# RasPi-BplusHAT.net
KiCad netlist of a schematic drawn in EAGLE
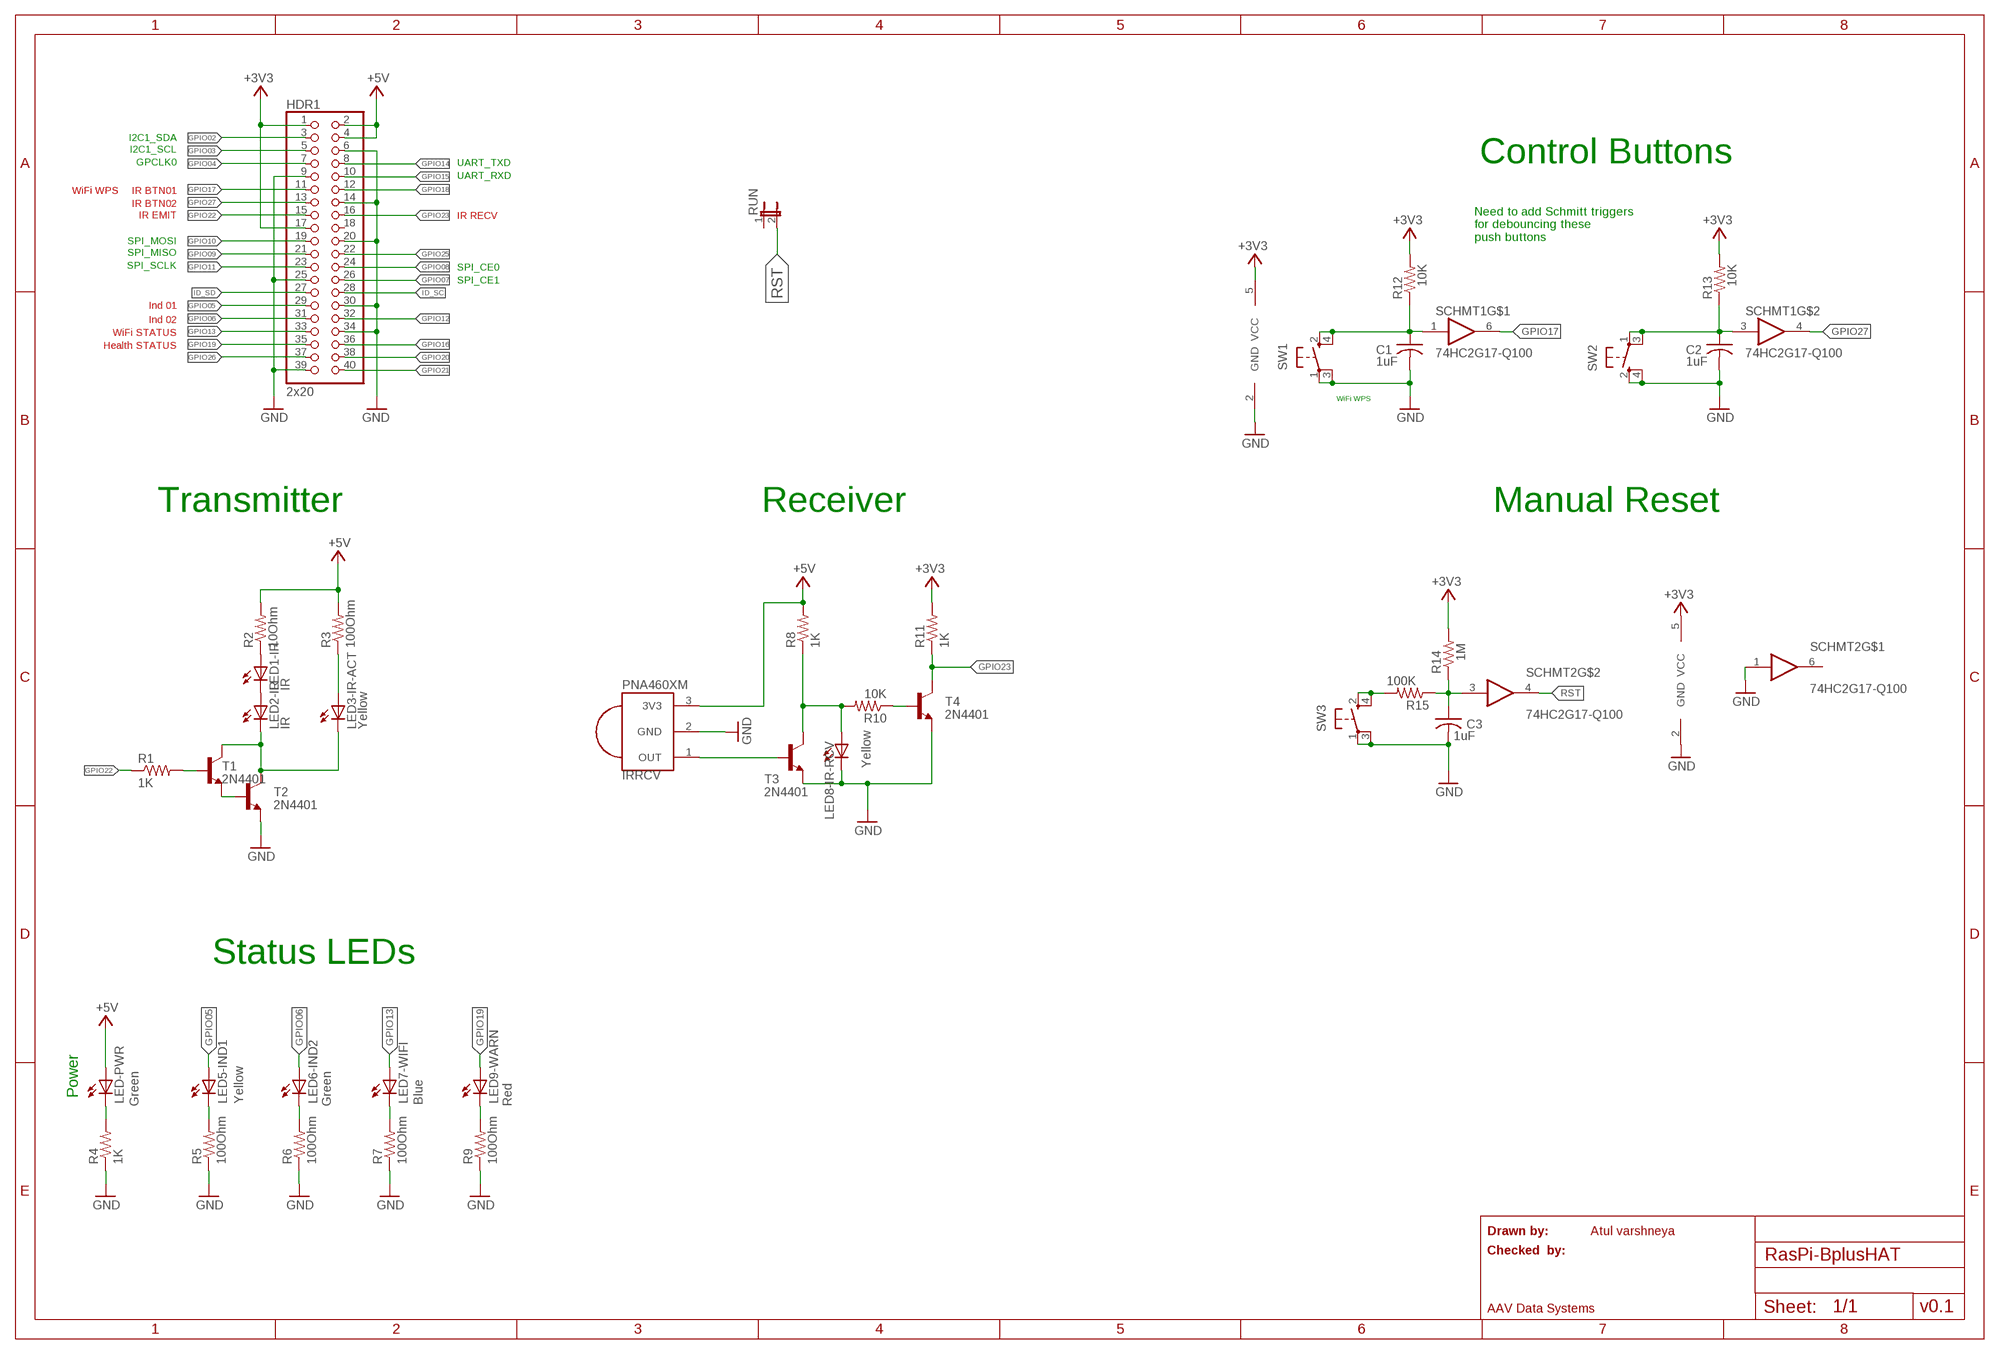
[diagram p0: schematic, sheet 1]

(export (version "E")
  (design (tool "Eeschema 10.0.6"))
  (components
    (comp (ref "C1")
      (value "1uF")
      (footprint "eagle-import:C0805")
      (fields (field (name "MPN") "MC0805B104K160CT"))
      (libsource (lib "eagle-import") (part "C-USC0805"))
    )
    (comp (ref "C2")
      (value "1uF")
      (footprint "eagle-import:C0805")
      (fields (field (name "MPN") "MC0805B104K160CT"))
      (libsource (lib "eagle-import") (part "C-USC0805"))
    )
    (comp (ref "C3")
      (value "1uF")
      (footprint "eagle-import:C0805")
      (fields (field (name "MPN") "MC0805B104K160CT"))
      (libsource (lib "eagle-import") (part "C-USC0805"))
    )
    (comp (ref "HDR1")
      (value "2x20")
      (footprint "eagle-import:2X20")
      (libsource (lib "eagle-import") (part "PINHD-2X20"))
    )
    (comp (ref "IRRCV")
      (value "PNA460XM")
      (footprint "eagle-import:PNA460XM")
      (fields (field (name "MPN") "TSOP38238"))
      (libsource (lib "eagle-import") (part "PNA460XM"))
    )
    (comp (ref "LED-PWR")
      (value "Green")
      (footprint "eagle-import:CHIPLED_0805")
      (fields (field (name "MPN") "150080GS75000"))
      (libsource (lib "eagle-import") (part "LEDCHIPLED_0805"))
    )
    (comp (ref "LED1-IR")
      (value "IR")
      (footprint "eagle-import:MICRO-SIDELED")
      (fields (field (name "MPN") "VSMB2943SLX01"))
      (libsource (lib "eagle-import") (part "LEDMICRO-SIDELED"))
    )
    (comp (ref "LED2-IR")
      (value "IR")
      (footprint "eagle-import:MICRO-SIDELED")
      (fields (field (name "MPN") "VSMB2943SLX01"))
      (libsource (lib "eagle-import") (part "LEDMICRO-SIDELED"))
    )
    (comp (ref "LED3-IR-ACT")
      (value "Yellow")
      (footprint "eagle-import:CHIPLED_0805")
      (fields (field (name "MPN") "150080YS75000"))
      (libsource (lib "eagle-import") (part "LEDCHIPLED_0805"))
    )
    (comp (ref "LED5-IND1")
      (value "Yellow")
      (footprint "eagle-import:CHIPLED_0805")
      (fields (field (name "MPN") "150080YS75000"))
      (libsource (lib "eagle-import") (part "LEDCHIPLED_0805"))
    )
    (comp (ref "LED6-IND2")
      (value "Green")
      (footprint "eagle-import:CHIPLED_0805")
      (fields (field (name "MPN") "150080GS75000"))
      (libsource (lib "eagle-import") (part "LEDCHIPLED_0805"))
    )
    (comp (ref "LED7-WIFI")
      (value "Blue")
      (footprint "eagle-import:CHIPLED_0805")
      (fields (field (name "MPN") "150080BS75000"))
      (libsource (lib "eagle-import") (part "LEDCHIPLED_0805"))
    )
    (comp (ref "LED8-IR-RCV")
      (value "Yellow")
      (footprint "eagle-import:CHIPLED_0805")
      (fields (field (name "MPN") "150080YS75000"))
      (libsource (lib "eagle-import") (part "LEDCHIPLED_0805"))
    )
    (comp (ref "LED9-WARN")
      (value "Red")
      (footprint "eagle-import:CHIPLED_0805")
      (fields (field (name "MPN") "150080RS75000"))
      (libsource (lib "eagle-import") (part "LEDCHIPLED_0805"))
    )
    (comp (ref "R1")
      (value "1K")
      (footprint "eagle-import:R0805")
      (fields (field (name "MF") "VISHAY/DALE") (field (name "MPN") "CRCW08051K00FKEA"))
      (libsource (lib "eagle-import") (part "R-US_R0805"))
    )
    (comp (ref "R2")
      (value "10Ohm")
      (footprint "eagle-import:R0805")
      (fields (field (name "MF") "VISHAY/DALE") (field (name "MPN") "CRCW080510R0FKEA"))
      (libsource (lib "eagle-import") (part "R-US_R0805"))
    )
    (comp (ref "R3")
      (value "100Ohm")
      (footprint "eagle-import:R0805")
      (fields (field (name "MF") "VISHAY/DALE") (field (name "MPN") "CRCW0805100RFKEA"))
      (libsource (lib "eagle-import") (part "R-US_R0805"))
    )
    (comp (ref "R4")
      (value "1K")
      (footprint "eagle-import:R0805")
      (fields (field (name "MF") "VISHAY/DALE") (field (name "MPN") "CRCW08051K00FKEA"))
      (libsource (lib "eagle-import") (part "R-US_R0805"))
    )
    (comp (ref "R5")
      (value "100Ohm")
      (footprint "eagle-import:R0805")
      (fields (field (name "MF") "VISHAY/DALE") (field (name "MPN") "CRCW0805100RFKEA"))
      (libsource (lib "eagle-import") (part "R-US_R0805"))
    )
    (comp (ref "R6")
      (value "100Ohm")
      (footprint "eagle-import:R0805")
      (fields (field (name "MF") "VISHAY/DALE") (field (name "MPN") "CRCW0805100RFKEA"))
      (libsource (lib "eagle-import") (part "R-US_R0805"))
    )
    (comp (ref "R7")
      (value "100Ohm")
      (footprint "eagle-import:R0805")
      (fields (field (name "MF") "VISHAY/DALE") (field (name "MPN") "CRCW0805100RFKEA"))
      (libsource (lib "eagle-import") (part "R-US_R0805"))
    )
    (comp (ref "R8")
      (value "1K")
      (footprint "eagle-import:R0805")
      (fields (field (name "MF") "VISHAY/DALE") (field (name "MPN") "CRCW08051K00FKEA"))
      (libsource (lib "eagle-import") (part "R-US_R0805"))
    )
    (comp (ref "R9")
      (value "100Ohm")
      (footprint "eagle-import:R0805")
      (fields (field (name "MF") "VISHAY/DALE") (field (name "MPN") "CRCW0805100RFKEA"))
      (libsource (lib "eagle-import") (part "R-US_R0805"))
    )
    (comp (ref "R10")
      (value "10K")
      (footprint "eagle-import:R0805")
      (fields (field (name "MF") "VISHAY/DALE") (field (name "MPN") "CRCW080510K0FKEA"))
      (libsource (lib "eagle-import") (part "R-US_R0805"))
    )
    (comp (ref "R11")
      (value "1K")
      (footprint "eagle-import:R0805")
      (fields (field (name "MF") "VISHAY/DALE") (field (name "MPN") "CRCW08051K00FKEA"))
      (libsource (lib "eagle-import") (part "R-US_R0805"))
    )
    (comp (ref "R12")
      (value "10K")
      (footprint "eagle-import:R0805")
      (fields (field (name "MF") "VISHAY/DALE") (field (name "MPN") "CRCW080510K0FKEA"))
      (libsource (lib "eagle-import") (part "R-US_R0805"))
    )
    (comp (ref "R13")
      (value "10K")
      (footprint "eagle-import:R0805")
      (fields (field (name "MF") "VISHAY/DALE") (field (name "MPN") "CRCW080510K0FKEA"))
      (libsource (lib "eagle-import") (part "R-US_R0805"))
    )
    (comp (ref "R14")
      (value "1M")
      (footprint "eagle-import:R0805")
      (fields (field (name "MF") "VISHAY/DALE") (field (name "MPN") "CRCW08051M00FKEA"))
      (libsource (lib "eagle-import") (part "R-US_R0805"))
    )
    (comp (ref "R15")
      (value "100K")
      (footprint "eagle-import:R0805")
      (fields (field (name "MF") "VISHAY/DALE") (field (name "MPN") "CRCW0805100KFKEA"))
      (libsource (lib "eagle-import") (part "R-US_R0805"))
    )
    (comp (ref "RUN")
      (value "RST")
      (footprint "eagle-import:JP1")
      (fields (field (name "MPN") "2211S-02G"))
      (libsource (lib "eagle-import") (part "JP1E"))
    )
    (comp (ref "SCHMT1")
      (value "74HC2G17-Q100")
      (footprint "eagle-import:SC-70-6L")
      (fields (field (name "MPN") "74HC2G17GW,125") (field (name "OC_NEWARK") "71R2196"))
      (libsource (lib "eagle-import") (part "74HC2G17-Q100"))
    )
    (comp (ref "SCHMT2")
      (value "74HC2G17-Q100")
      (footprint "eagle-import:SC-70-6L")
      (fields (field (name "MPN") "74HC2G17GW,125") (field (name "OC_NEWARK") "71R2196"))
      (libsource (lib "eagle-import") (part "74HC2G17-Q100"))
    )
    (comp (ref "SW1")
      (value "SPST_TACT-KMR2")
      (footprint "eagle-import:KMR2")
      (libsource (lib "eagle-import") (part "SPST_TACT-KMR2"))
    )
    (comp (ref "SW2")
      (value "SPST_TACT-KMR2")
      (footprint "eagle-import:KMR2")
      (libsource (lib "eagle-import") (part "SPST_TACT-KMR2"))
    )
    (comp (ref "SW3")
      (value "SPST_TACT-KMR2")
      (footprint "eagle-import:KMR2")
      (libsource (lib "eagle-import") (part "SPST_TACT-KMR2"))
    )
    (comp (ref "T1")
      (value "2N4401")
      (footprint "eagle-import:SOT23-BEC")
      (fields (field (name "MPN") "MMBT4401-TP"))
      (libsource (lib "eagle-import") (part "transistor-neu-to92_-NPN-SOT23-BECMMBT4401LT1"))
    )
    (comp (ref "T2")
      (value "2N4401")
      (footprint "eagle-import:SOT23-BEC")
      (fields (field (name "MPN") "MMBT4401-TP"))
      (libsource (lib "eagle-import") (part "transistor-neu-to92_-NPN-SOT23-BECMMBT4401LT1"))
    )
    (comp (ref "T3")
      (value "2N4401")
      (footprint "eagle-import:SOT23-BEC")
      (fields (field (name "MPN") "MMBT4401-TP"))
      (libsource (lib "eagle-import") (part "-NPN-SOT23-BECMMBT4401LT1"))
    )
    (comp (ref "T4")
      (value "2N4401")
      (footprint "eagle-import:SOT23-BEC")
      (fields (field (name "MPN") "MMBT4401-TP"))
      (libsource (lib "eagle-import") (part "-NPN-SOT23-BECMMBT4401LT1"))
    )
  )
  (nets
    (net (code "1") (name "+3V3") (class "Default")
      (node (ref "HDR1") (pin "1") (pinfunction "1_1") (pintype "passive"))
      (node (ref "HDR1") (pin "17") (pinfunction "17_17") (pintype "passive"))
      (node (ref "R11") (pin "2") (pinfunction "2_2") (pintype "passive"))
      (node (ref "R12") (pin "2") (pinfunction "2_2") (pintype "passive"))
      (node (ref "R13") (pin "2") (pinfunction "2_2") (pintype "passive"))
      (node (ref "R14") (pin "2") (pinfunction "2_2") (pintype "passive"))
      (node (ref "SCHMT1") (pin "5") (pinfunction "VCC_5") (pintype "bidirectional"))
      (node (ref "SCHMT2") (pin "5") (pinfunction "VCC_5") (pintype "bidirectional"))
    )
    (net (code "2") (name "+5V") (class "Default")
      (node (ref "HDR1") (pin "2") (pinfunction "2_2") (pintype "passive"))
      (node (ref "HDR1") (pin "4") (pinfunction "4_4") (pintype "passive"))
      (node (ref "IRRCV") (pin "3") (pinfunction "3V3_3") (pintype "power_in"))
      (node (ref "LED-PWR") (pin "A") (pinfunction "A_A") (pintype "passive"))
      (node (ref "R2") (pin "2") (pinfunction "2_2") (pintype "passive"))
      (node (ref "R3") (pin "2") (pinfunction "2_2") (pintype "passive"))
      (node (ref "R8") (pin "2") (pinfunction "2_2") (pintype "passive"))
    )
    (net (code "3") (name "GND") (class "Default")
      (node (ref "C1") (pin "2") (pinfunction "2_2") (pintype "passive"))
      (node (ref "C2") (pin "2") (pinfunction "2_2") (pintype "passive"))
      (node (ref "C3") (pin "2") (pinfunction "2_2") (pintype "passive"))
      (node (ref "HDR1") (pin "14") (pinfunction "14_14") (pintype "passive"))
      (node (ref "HDR1") (pin "20") (pinfunction "20_20") (pintype "passive"))
      (node (ref "HDR1") (pin "25") (pinfunction "25_25") (pintype "passive"))
      (node (ref "HDR1") (pin "30") (pinfunction "30_30") (pintype "passive"))
      (node (ref "HDR1") (pin "34") (pinfunction "34_34") (pintype "passive"))
      (node (ref "HDR1") (pin "39") (pinfunction "39_39") (pintype "passive"))
      (node (ref "HDR1") (pin "6") (pinfunction "6_6") (pintype "passive"))
      (node (ref "HDR1") (pin "9") (pinfunction "9_9") (pintype "passive"))
      (node (ref "IRRCV") (pin "2") (pinfunction "GND_2") (pintype "power_in"))
      (node (ref "LED8-IR-RCV") (pin "C") (pinfunction "C_C") (pintype "passive"))
      (node (ref "R4") (pin "1") (pinfunction "1_1") (pintype "passive"))
      (node (ref "R5") (pin "1") (pinfunction "1_1") (pintype "passive"))
      (node (ref "R6") (pin "1") (pinfunction "1_1") (pintype "passive"))
      (node (ref "R7") (pin "1") (pinfunction "1_1") (pintype "passive"))
      (node (ref "R9") (pin "1") (pinfunction "1_1") (pintype "passive"))
      (node (ref "SCHMT1") (pin "2") (pinfunction "GND_2") (pintype "bidirectional"))
      (node (ref "SCHMT2") (pin "1") (pinfunction "I_1") (pintype "input"))
      (node (ref "SCHMT2") (pin "2") (pinfunction "GND_2") (pintype "bidirectional"))
      (node (ref "SW1") (pin "1") (pinfunction "P_1") (pintype "passive"))
      (node (ref "SW1") (pin "3") (pinfunction "P1_3") (pintype "passive"))
      (node (ref "SW2") (pin "2") (pinfunction "S_2") (pintype "passive"))
      (node (ref "SW2") (pin "4") (pinfunction "S1_4") (pintype "passive"))
      (node (ref "SW3") (pin "1") (pinfunction "P_1") (pintype "passive"))
      (node (ref "SW3") (pin "3") (pinfunction "P1_3") (pintype "passive"))
      (node (ref "T2") (pin "E") (pinfunction "E_E") (pintype "passive"))
      (node (ref "T3") (pin "E") (pinfunction "E_E") (pintype "passive"))
      (node (ref "T4") (pin "E") (pinfunction "E_E") (pintype "passive"))
    )
    (net (code "4") (name "GPIO02") (class "Default")
      (node (ref "HDR1") (pin "3") (pinfunction "3_3") (pintype "passive"))
    )
    (net (code "5") (name "GPIO03") (class "Default")
      (node (ref "HDR1") (pin "5") (pinfunction "5_5") (pintype "passive"))
    )
    (net (code "6") (name "GPIO04") (class "Default")
      (node (ref "HDR1") (pin "7") (pinfunction "7_7") (pintype "passive"))
    )
    (net (code "7") (name "GPIO05") (class "Default")
      (node (ref "HDR1") (pin "29") (pinfunction "29_29") (pintype "passive"))
      (node (ref "LED5-IND1") (pin "A") (pinfunction "A_A") (pintype "passive"))
    )
    (net (code "8") (name "GPIO06") (class "Default")
      (node (ref "HDR1") (pin "31") (pinfunction "31_31") (pintype "passive"))
      (node (ref "LED6-IND2") (pin "A") (pinfunction "A_A") (pintype "passive"))
    )
    (net (code "9") (name "GPIO07") (class "Default")
      (node (ref "HDR1") (pin "26") (pinfunction "26_26") (pintype "passive"))
    )
    (net (code "10") (name "GPIO08") (class "Default")
      (node (ref "HDR1") (pin "24") (pinfunction "24_24") (pintype "passive"))
    )
    (net (code "11") (name "GPIO09") (class "Default")
      (node (ref "HDR1") (pin "21") (pinfunction "21_21") (pintype "passive"))
    )
    (net (code "12") (name "GPIO10") (class "Default")
      (node (ref "HDR1") (pin "19") (pinfunction "19_19") (pintype "passive"))
    )
    (net (code "13") (name "GPIO11") (class "Default")
      (node (ref "HDR1") (pin "23") (pinfunction "23_23") (pintype "passive"))
    )
    (net (code "14") (name "GPIO12") (class "Default")
      (node (ref "HDR1") (pin "32") (pinfunction "32_32") (pintype "passive"))
    )
    (net (code "15") (name "GPIO13") (class "Default")
      (node (ref "HDR1") (pin "33") (pinfunction "33_33") (pintype "passive"))
      (node (ref "LED7-WIFI") (pin "A") (pinfunction "A_A") (pintype "passive"))
    )
    (net (code "16") (name "GPIO14") (class "Default")
      (node (ref "HDR1") (pin "8") (pinfunction "8_8") (pintype "passive"))
    )
    (net (code "17") (name "GPIO15") (class "Default")
      (node (ref "HDR1") (pin "10") (pinfunction "10_10") (pintype "passive"))
    )
    (net (code "18") (name "GPIO16") (class "Default")
      (node (ref "HDR1") (pin "36") (pinfunction "36_36") (pintype "passive"))
    )
    (net (code "19") (name "GPIO17") (class "Default")
      (node (ref "HDR1") (pin "11") (pinfunction "11_11") (pintype "passive"))
      (node (ref "SCHMT1") (pin "6") (pinfunction "O_6") (pintype "output"))
    )
    (net (code "20") (name "GPIO18") (class "Default")
      (node (ref "HDR1") (pin "12") (pinfunction "12_12") (pintype "passive"))
    )
    (net (code "21") (name "GPIO19") (class "Default")
      (node (ref "HDR1") (pin "35") (pinfunction "35_35") (pintype "passive"))
      (node (ref "LED9-WARN") (pin "A") (pinfunction "A_A") (pintype "passive"))
    )
    (net (code "22") (name "GPIO20") (class "Default")
      (node (ref "HDR1") (pin "38") (pinfunction "38_38") (pintype "passive"))
    )
    (net (code "23") (name "GPIO21") (class "Default")
      (node (ref "HDR1") (pin "40") (pinfunction "40_40") (pintype "passive"))
    )
    (net (code "24") (name "GPIO22") (class "Default")
      (node (ref "HDR1") (pin "15") (pinfunction "15_15") (pintype "passive"))
      (node (ref "R1") (pin "1") (pinfunction "1_1") (pintype "passive"))
    )
    (net (code "25") (name "GPIO23") (class "Default")
      (node (ref "HDR1") (pin "16") (pinfunction "16_16") (pintype "passive"))
      (node (ref "R11") (pin "1") (pinfunction "1_1") (pintype "passive"))
      (node (ref "T4") (pin "C") (pinfunction "C_C") (pintype "passive"))
    )
    (net (code "26") (name "GPIO25") (class "Default")
      (node (ref "HDR1") (pin "22") (pinfunction "22_22") (pintype "passive"))
    )
    (net (code "27") (name "GPIO26") (class "Default")
      (node (ref "HDR1") (pin "37") (pinfunction "37_37") (pintype "passive"))
    )
    (net (code "28") (name "GPIO27") (class "Default")
      (node (ref "HDR1") (pin "13") (pinfunction "13_13") (pintype "passive"))
      (node (ref "SCHMT1") (pin "4") (pinfunction "O_4") (pintype "output"))
    )
    (net (code "29") (name "ID_SC") (class "Default")
      (node (ref "HDR1") (pin "28") (pinfunction "28_28") (pintype "passive"))
    )
    (net (code "30") (name "ID_SD") (class "Default")
      (node (ref "HDR1") (pin "27") (pinfunction "27_27") (pintype "passive"))
    )
    (net (code "31") (name "Net-(IRRCV-OUT)") (class "Default")
      (node (ref "IRRCV") (pin "1") (pinfunction "OUT_1") (pintype "output"))
      (node (ref "T3") (pin "B") (pinfunction "B_B") (pintype "passive"))
    )
    (net (code "32") (name "Net-(LED-PWR-PadC)") (class "Default")
      (node (ref "LED-PWR") (pin "C") (pinfunction "C_C") (pintype "passive"))
      (node (ref "R4") (pin "2") (pinfunction "2_2") (pintype "passive"))
    )
    (net (code "33") (name "Net-(LED1-IR-PadA)") (class "Default")
      (node (ref "LED1-IR") (pin "A") (pinfunction "A_A") (pintype "passive"))
      (node (ref "R2") (pin "1") (pinfunction "1_1") (pintype "passive"))
    )
    (net (code "34") (name "Net-(LED1-IR-PadC)") (class "Default")
      (node (ref "LED1-IR") (pin "C") (pinfunction "C_C") (pintype "passive"))
      (node (ref "LED2-IR") (pin "A") (pinfunction "A_A") (pintype "passive"))
    )
    (net (code "35") (name "Net-(LED2-IR-PadC)") (class "Default")
      (node (ref "LED2-IR") (pin "C") (pinfunction "C_C") (pintype "passive"))
      (node (ref "LED3-IR-ACT") (pin "C") (pinfunction "C_C") (pintype "passive"))
      (node (ref "T1") (pin "C") (pinfunction "C_C") (pintype "passive"))
      (node (ref "T2") (pin "C") (pinfunction "C_C") (pintype "passive"))
    )
    (net (code "36") (name "Net-(LED3-IR-ACT-PadA)") (class "Default")
      (node (ref "LED3-IR-ACT") (pin "A") (pinfunction "A_A") (pintype "passive"))
      (node (ref "R3") (pin "1") (pinfunction "1_1") (pintype "passive"))
    )
    (net (code "37") (name "Net-(LED5-IND1-PadC)") (class "Default")
      (node (ref "LED5-IND1") (pin "C") (pinfunction "C_C") (pintype "passive"))
      (node (ref "R5") (pin "2") (pinfunction "2_2") (pintype "passive"))
    )
    (net (code "38") (name "Net-(LED6-IND2-PadC)") (class "Default")
      (node (ref "LED6-IND2") (pin "C") (pinfunction "C_C") (pintype "passive"))
      (node (ref "R6") (pin "2") (pinfunction "2_2") (pintype "passive"))
    )
    (net (code "39") (name "Net-(LED7-WIFI-PadC)") (class "Default")
      (node (ref "LED7-WIFI") (pin "C") (pinfunction "C_C") (pintype "passive"))
      (node (ref "R7") (pin "2") (pinfunction "2_2") (pintype "passive"))
    )
    (net (code "40") (name "Net-(LED8-IR-RCV-PadA)") (class "Default")
      (node (ref "LED8-IR-RCV") (pin "A") (pinfunction "A_A") (pintype "passive"))
      (node (ref "R10") (pin "2") (pinfunction "2_2") (pintype "passive"))
      (node (ref "R8") (pin "1") (pinfunction "1_1") (pintype "passive"))
      (node (ref "T3") (pin "C") (pinfunction "C_C") (pintype "passive"))
    )
    (net (code "41") (name "Net-(LED9-WARN-PadC)") (class "Default")
      (node (ref "LED9-WARN") (pin "C") (pinfunction "C_C") (pintype "passive"))
      (node (ref "R9") (pin "2") (pinfunction "2_2") (pintype "passive"))
    )
    (net (code "42") (name "Net-(R1-Pad2)") (class "Default")
      (node (ref "R1") (pin "2") (pinfunction "2_2") (pintype "passive"))
      (node (ref "T1") (pin "B") (pinfunction "B_B") (pintype "passive"))
    )
    (net (code "43") (name "Net-(R10-Pad1)") (class "Default")
      (node (ref "R10") (pin "1") (pinfunction "1_1") (pintype "passive"))
      (node (ref "T4") (pin "B") (pinfunction "B_B") (pintype "passive"))
    )
    (net (code "44") (name "Net-(SCHMT1A-I)") (class "Default")
      (node (ref "C1") (pin "1") (pinfunction "1_1") (pintype "passive"))
      (node (ref "R12") (pin "1") (pinfunction "1_1") (pintype "passive"))
      (node (ref "SCHMT1") (pin "1") (pinfunction "I_1") (pintype "input"))
      (node (ref "SW1") (pin "2") (pinfunction "S_2") (pintype "passive"))
      (node (ref "SW1") (pin "4") (pinfunction "S1_4") (pintype "passive"))
    )
    (net (code "45") (name "Net-(SCHMT1B-I)") (class "Default")
      (node (ref "C2") (pin "1") (pinfunction "1_1") (pintype "passive"))
      (node (ref "R13") (pin "1") (pinfunction "1_1") (pintype "passive"))
      (node (ref "SCHMT1") (pin "3") (pinfunction "I_3") (pintype "input"))
      (node (ref "SW2") (pin "1") (pinfunction "P_1") (pintype "passive"))
      (node (ref "SW2") (pin "3") (pinfunction "P1_3") (pintype "passive"))
    )
    (net (code "46") (name "Net-(SCHMT2B-I)") (class "Default")
      (node (ref "C3") (pin "1") (pinfunction "1_1") (pintype "passive"))
      (node (ref "R14") (pin "1") (pinfunction "1_1") (pintype "passive"))
      (node (ref "R15") (pin "1") (pinfunction "1_1") (pintype "passive"))
      (node (ref "SCHMT2") (pin "3") (pinfunction "I_3") (pintype "input"))
    )
    (net (code "47") (name "Net-(SW3-S)") (class "Default")
      (node (ref "R15") (pin "2") (pinfunction "2_2") (pintype "passive"))
      (node (ref "SW3") (pin "2") (pinfunction "S_2") (pintype "passive"))
      (node (ref "SW3") (pin "4") (pinfunction "S1_4") (pintype "passive"))
    )
    (net (code "48") (name "Net-(T1-PadE)") (class "Default")
      (node (ref "T1") (pin "E") (pinfunction "E_E") (pintype "passive"))
      (node (ref "T2") (pin "B") (pinfunction "B_B") (pintype "passive"))
    )
    (net (code "49") (name "RST") (class "Default")
      (node (ref "RUN") (pin "2") (pinfunction "2_2") (pintype "passive"))
      (node (ref "SCHMT2") (pin "4") (pinfunction "O_4") (pintype "output"))
    )
    (net (code "50") (name "unconnected-(HDR1-Pad18)") (class "Default")
      (node (ref "HDR1") (pin "18") (pinfunction "18_18") (pintype "passive"))
    )
    (net (code "51") (name "unconnected-(RUN-Pad1)") (class "Default")
      (node (ref "RUN") (pin "1") (pinfunction "1_1") (pintype "passive"))
    )
    (net (code "52") (name "unconnected-(SCHMT2A-O-Pad6)") (class "Default")
      (node (ref "SCHMT2") (pin "6") (pinfunction "O_6") (pintype "output"))
    )
  )
)
